# og14u.net
KiCad netlist of a schematic drawn in EAGLE
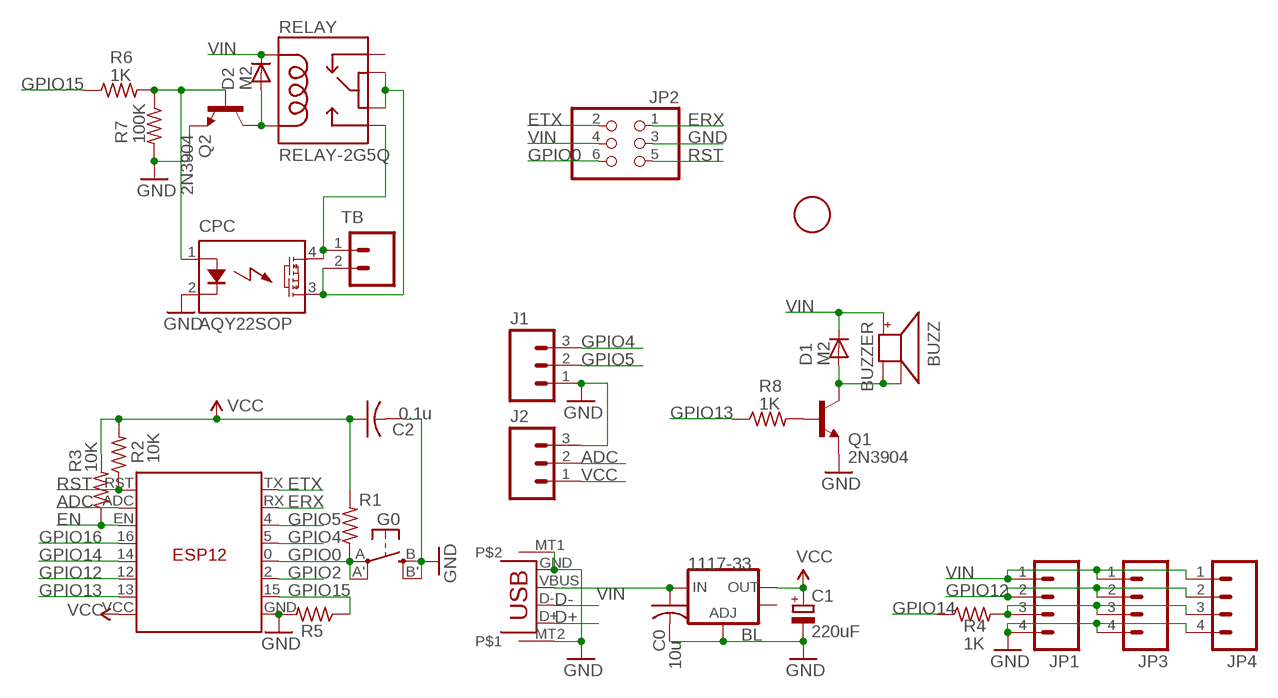
[diagram p0: schematic, sheet 1]

(export (version "E")
  (design (tool "Eeschema 10.0.6"))
  (components
    (comp (ref "1F")
      (value "FIDUCIAL")
      (footprint "eagle-import:FIDUCIAL_1MM")
      (libsource (lib "eagle-import") (part "FIDUCIAL"))
    )
    (comp (ref "BL")
      (value "1117-33")
      (footprint "eagle-import:SOT223")
      (libsource (lib "eagle-import") (part "V_REG_LM1117SOT223"))
    )
    (comp (ref "BUZZ")
      (value "BUZZER")
      (footprint "eagle-import:SMT-8585-BUZZER")
      (libsource (lib "eagle-import") (part "BUZZER"))
    )
    (comp (ref "C0")
      (value "10u")
      (footprint "eagle-import:C0805K")
      (libsource (lib "eagle-import") (part "C-USC0805K"))
    )
    (comp (ref "C1")
      (value "220uF")
      (footprint "eagle-import:B_3528-21R")
      (libsource (lib "eagle-import") (part "CPOL-EUB/3528-21R"))
    )
    (comp (ref "C2")
      (value "0.1u")
      (footprint "eagle-import:C0603K")
      (libsource (lib "eagle-import") (part "C-USC0603K"))
    )
    (comp (ref "CPC")
      (value "AQY22SOP")
      (footprint "eagle-import:SOP04")
      (libsource (lib "eagle-import") (part "AQYSOP22"))
    )
    (comp (ref "D1")
      (value "M2")
      (footprint "eagle-import:DO-214AC")
      (libsource (lib "eagle-import") (part "DIODE-DO-214AC"))
    )
    (comp (ref "D2")
      (value "M2")
      (footprint "eagle-import:DO-214AC")
      (libsource (lib "eagle-import") (part "DIODE-DO-214AC"))
    )
    (comp (ref "ESP")
      (value "ESP12")
      (footprint "eagle-import:ESP12")
      (libsource (lib "eagle-import") (part "ESP12"))
    )
    (comp (ref "G0")
      (value "SPST_TACT-EVQQ2")
      (footprint "eagle-import:EVQ-Q2")
      (libsource (lib "eagle-import") (part "SPST_TACT-EVQQ2"))
    )
    (comp (ref "J1")
      (value "M03PTH")
      (footprint "eagle-import:1X03")
      (libsource (lib "eagle-import") (part "M03PTH"))
    )
    (comp (ref "J2")
      (value "M03PTH")
      (footprint "eagle-import:1X03")
      (libsource (lib "eagle-import") (part "M03PTH"))
    )
    (comp (ref "JP1")
      (value "M04SONICSMD")
      (footprint "eagle-import:1X04_SONICSENSOR_SMD")
      (libsource (lib "eagle-import") (part "M04SONICSMD"))
    )
    (comp (ref "JP2")
      (value "PINHD-2X3")
      (footprint "eagle-import:2X03")
      (libsource (lib "eagle-import") (part "PINHD-2X3"))
    )
    (comp (ref "JP3")
      (value "M04DIST")
      (footprint "eagle-import:1X04_NO_SILK_DIST")
      (libsource (lib "eagle-import") (part "M04DIST"))
    )
    (comp (ref "JP4")
      (value "M04DIST")
      (footprint "eagle-import:1X04_NO_SILK_DIST")
      (libsource (lib "eagle-import") (part "M04DIST"))
    )
    (comp (ref "Q1")
      (value "2N3904")
      (footprint "eagle-import:SOT23-3")
      (libsource (lib "eagle-import") (part "TRANSISTOR_NPNSOT23-3"))
    )
    (comp (ref "Q2")
      (value "2N3904")
      (footprint "eagle-import:SOT23-3")
      (libsource (lib "eagle-import") (part "TRANSISTOR_NPNSOT23-3"))
    )
    (comp (ref "R1")
      (value "10K")
      (footprint "eagle-import:R0603")
      (libsource (lib "eagle-import") (part "R-US_R0603"))
    )
    (comp (ref "R2")
      (value "10K")
      (footprint "eagle-import:R0603")
      (libsource (lib "eagle-import") (part "R-US_R0603"))
    )
    (comp (ref "R3")
      (value "10K")
      (footprint "eagle-import:R0603")
      (libsource (lib "eagle-import") (part "R-US_R0603"))
    )
    (comp (ref "R4")
      (value "1K")
      (footprint "eagle-import:R0603")
      (libsource (lib "eagle-import") (part "adafruit2013_R-US_R0603"))
    )
    (comp (ref "R5")
      (value "10K")
      (footprint "eagle-import:R0603")
      (libsource (lib "eagle-import") (part "R-US_R0603"))
    )
    (comp (ref "R6")
      (value "1K")
      (footprint "eagle-import:R0603")
      (libsource (lib "eagle-import") (part "adafruit2013_R-US_R0603"))
    )
    (comp (ref "R7")
      (value "100K")
      (footprint "eagle-import:R0603")
      (libsource (lib "eagle-import") (part "adafruit2013_R-US_R0603"))
    )
    (comp (ref "R8")
      (value "1K")
      (footprint "eagle-import:R0603")
      (libsource (lib "eagle-import") (part "adafruit2013_R-US_R0603"))
    )
    (comp (ref "RELAY")
      (value "RELAY-2G5Q")
      (footprint "eagle-import:RELAY-G5V")
      (libsource (lib "eagle-import") (part "RELAY-2G5Q"))
    )
    (comp (ref "TB")
      (value "OPENER")
      (footprint "eagle-import:SCREWTERMINAL-5MM-2-KF")
      (libsource (lib "eagle-import") (part "M02KF"))
    )
    (comp (ref "X3")
      (value "USB+GND")
      (footprint "eagle-import:USB-MICROB2")
      (libsource (lib "eagle-import") (part "USB+GND"))
    )
  )
  (nets
    (net (code "1") (name "/ADC") (class "Default")
      (node (ref "ESP") (pin "ADC") (pinfunction "ADC_ADC") (pintype "bidirectional"))
      (node (ref "J2") (pin "2") (pinfunction "2_2") (pintype "passive"))
    )
    (net (code "2") (name "/D+") (class "Default")
      (node (ref "X3") (pin "D+") (pinfunction "D+_D+") (pintype "bidirectional"))
    )
    (net (code "3") (name "/D-") (class "Default")
      (node (ref "X3") (pin "D-") (pinfunction "D-_D-") (pintype "bidirectional"))
    )
    (net (code "4") (name "/EN") (class "Default")
      (node (ref "ESP") (pin "EN") (pinfunction "EN_EN") (pintype "bidirectional"))
      (node (ref "R3") (pin "1") (pinfunction "1_1") (pintype "passive"))
    )
    (net (code "5") (name "/ERX") (class "Default")
      (node (ref "ESP") (pin "RX") (pinfunction "RX_RX") (pintype "bidirectional"))
      (node (ref "JP2") (pin "1") (pinfunction "1_1") (pintype "passive"))
    )
    (net (code "6") (name "/ETX") (class "Default")
      (node (ref "ESP") (pin "TX") (pinfunction "TX_TX") (pintype "bidirectional"))
      (node (ref "JP2") (pin "2") (pinfunction "2_2") (pintype "passive"))
    )
    (net (code "7") (name "/GPIO0") (class "Default")
      (node (ref "ESP") (pin "0") (pinfunction "G0_0") (pintype "bidirectional"))
      (node (ref "G0") (pin "A") (pinfunction "P_A") (pintype "passive"))
      (node (ref "G0") (pin "A'") (pinfunction "P1_A'") (pintype "passive"))
      (node (ref "JP2") (pin "6") (pinfunction "6_6") (pintype "passive"))
      (node (ref "R1") (pin "1") (pinfunction "1_1") (pintype "passive"))
    )
    (net (code "8") (name "/GPIO2") (class "Default")
      (node (ref "ESP") (pin "2") (pinfunction "G2_2") (pintype "bidirectional"))
    )
    (net (code "9") (name "/GPIO4") (class "Default")
      (node (ref "ESP") (pin "5") (pinfunction "G5_5") (pintype "bidirectional"))
      (node (ref "J1") (pin "3") (pinfunction "3_3") (pintype "passive"))
    )
    (net (code "10") (name "/GPIO5") (class "Default")
      (node (ref "ESP") (pin "4") (pinfunction "G4_4") (pintype "bidirectional"))
      (node (ref "J1") (pin "2") (pinfunction "2_2") (pintype "passive"))
    )
    (net (code "11") (name "/GPIO12") (class "Default")
      (node (ref "ESP") (pin "12") (pinfunction "G12_12") (pintype "bidirectional"))
      (node (ref "JP1") (pin "2") (pinfunction "2_2") (pintype "passive"))
      (node (ref "JP3") (pin "2") (pinfunction "2_2") (pintype "passive"))
      (node (ref "JP4") (pin "2") (pinfunction "2_2") (pintype "passive"))
    )
    (net (code "12") (name "/GPIO13") (class "Default")
      (node (ref "ESP") (pin "13") (pinfunction "G13_13") (pintype "bidirectional"))
      (node (ref "R8") (pin "1") (pinfunction "1_1") (pintype "passive"))
    )
    (net (code "13") (name "/GPIO14") (class "Default")
      (node (ref "ESP") (pin "14") (pinfunction "G14_14") (pintype "bidirectional"))
      (node (ref "R4") (pin "1") (pinfunction "1_1") (pintype "passive"))
    )
    (net (code "14") (name "/GPIO15") (class "Default")
      (node (ref "ESP") (pin "15") (pinfunction "G15_15") (pintype "bidirectional"))
      (node (ref "R5") (pin "1") (pinfunction "1_1") (pintype "passive"))
      (node (ref "R6") (pin "1") (pinfunction "1_1") (pintype "passive"))
    )
    (net (code "15") (name "/GPIO16") (class "Default")
      (node (ref "ESP") (pin "16") (pinfunction "G16_16") (pintype "bidirectional"))
    )
    (net (code "16") (name "/RST") (class "Default")
      (node (ref "ESP") (pin "RST") (pinfunction "RST_RST") (pintype "bidirectional"))
      (node (ref "JP2") (pin "5") (pinfunction "5_5") (pintype "passive"))
      (node (ref "R2") (pin "1") (pinfunction "1_1") (pintype "passive"))
    )
    (net (code "17") (name "/VIN") (class "Default")
      (node (ref "BL") (pin "3") (pinfunction "IN_3") (pintype "input"))
      (node (ref "BUZZ") (pin "+") (pinfunction "+_+") (pintype "passive"))
      (node (ref "C0") (pin "1") (pinfunction "1_1") (pintype "passive"))
      (node (ref "D1") (pin "C") (pinfunction "C_C") (pintype "passive"))
      (node (ref "D2") (pin "C") (pinfunction "C_C") (pintype "passive"))
      (node (ref "JP1") (pin "1") (pinfunction "1_1") (pintype "passive"))
      (node (ref "JP2") (pin "4") (pinfunction "4_4") (pintype "passive"))
      (node (ref "JP3") (pin "1") (pinfunction "1_1") (pintype "passive"))
      (node (ref "JP4") (pin "1") (pinfunction "1_1") (pintype "passive"))
      (node (ref "RELAY") (pin "2") (pinfunction "2_2") (pintype "bidirectional"))
      (node (ref "X3") (pin "VBUS") (pinfunction "VBUS_VBUS") (pintype "bidirectional"))
    )
    (net (code "18") (name "GND") (class "Default")
      (node (ref "BL") (pin "1") (pinfunction "ADJ_1") (pintype "input"))
      (node (ref "C0") (pin "2") (pinfunction "2_2") (pintype "passive"))
      (node (ref "C1") (pin "-") (pinfunction "-_-") (pintype "passive"))
      (node (ref "C2") (pin "2") (pinfunction "2_2") (pintype "passive"))
      (node (ref "CPC") (pin "2") (pinfunction "K_2") (pintype "passive"))
      (node (ref "ESP") (pin "GND") (pinfunction "GND_GND") (pintype "power_in"))
      (node (ref "G0") (pin "B") (pinfunction "S_B") (pintype "passive"))
      (node (ref "G0") (pin "B'") (pinfunction "S1_B'") (pintype "passive"))
      (node (ref "J1") (pin "1") (pinfunction "1_1") (pintype "passive"))
      (node (ref "J2") (pin "3") (pinfunction "3_3") (pintype "passive"))
      (node (ref "JP1") (pin "4") (pinfunction "4_4") (pintype "passive"))
      (node (ref "JP2") (pin "3") (pinfunction "3_3") (pintype "passive"))
      (node (ref "JP3") (pin "4") (pinfunction "4_4") (pintype "passive"))
      (node (ref "JP4") (pin "4") (pinfunction "4_4") (pintype "passive"))
      (node (ref "Q1") (pin "2") (pinfunction "E_2") (pintype "passive"))
      (node (ref "Q2") (pin "2") (pinfunction "E_2") (pintype "passive"))
      (node (ref "R5") (pin "2") (pinfunction "2_2") (pintype "passive"))
      (node (ref "R7") (pin "2") (pinfunction "2_2") (pintype "passive"))
      (node (ref "X3") (pin "GND") (pinfunction "GND_GND") (pintype "bidirectional"))
      (node (ref "X3") (pin "MT1") (pinfunction "P$2_MT1") (pintype "bidirectional"))
      (node (ref "X3") (pin "MT2") (pinfunction "P$1_MT2") (pintype "bidirectional"))
    )
    (net (code "19") (name "Net-(CPC-A)") (class "Default")
      (node (ref "CPC") (pin "1") (pinfunction "A_1") (pintype "passive"))
      (node (ref "Q2") (pin "1") (pinfunction "B_1") (pintype "passive"))
      (node (ref "R6") (pin "2") (pinfunction "2_2") (pintype "passive"))
      (node (ref "R7") (pin "1") (pinfunction "1_1") (pintype "passive"))
    )
    (net (code "20") (name "Net-(CPC-DS1)") (class "Default")
      (node (ref "CPC") (pin "4") (pinfunction "DS1_4") (pintype "passive"))
      (node (ref "RELAY") (pin "10") (pinfunction "10_10") (pintype "bidirectional"))
      (node (ref "TB") (pin "1") (pinfunction "1_1") (pintype "passive"))
    )
    (net (code "21") (name "Net-(CPC-DS2)") (class "Default")
      (node (ref "CPC") (pin "3") (pinfunction "DS2_3") (pintype "passive"))
      (node (ref "RELAY") (pin "5") (pinfunction "5_5") (pintype "bidirectional"))
      (node (ref "RELAY") (pin "6") (pinfunction "6_6") (pintype "bidirectional"))
      (node (ref "TB") (pin "2") (pinfunction "2_2") (pintype "passive"))
    )
    (net (code "22") (name "Net-(JP1-Pad3)") (class "Default")
      (node (ref "JP1") (pin "3") (pinfunction "3_3") (pintype "passive"))
      (node (ref "JP3") (pin "3") (pinfunction "3_3") (pintype "passive"))
      (node (ref "JP4") (pin "3") (pinfunction "3_3") (pintype "passive"))
      (node (ref "R4") (pin "2") (pinfunction "2_2") (pintype "passive"))
    )
    (net (code "23") (name "Net-(Q1-B)") (class "Default")
      (node (ref "Q1") (pin "1") (pinfunction "B_1") (pintype "passive"))
      (node (ref "R8") (pin "2") (pinfunction "2_2") (pintype "passive"))
    )
    (net (code "24") (name "Net-(Q1-C)") (class "Default")
      (node (ref "BUZZ") (pin "-") (pinfunction "-_-") (pintype "passive"))
      (node (ref "BUZZ") (pin "A-") (pinfunction "A-_A-") (pintype "passive"))
      (node (ref "D1") (pin "A") (pinfunction "A_A") (pintype "passive"))
      (node (ref "Q1") (pin "3") (pinfunction "C_3") (pintype "passive"))
    )
    (net (code "25") (name "Net-(Q2-C)") (class "Default")
      (node (ref "D2") (pin "A") (pinfunction "A_A") (pintype "passive"))
      (node (ref "Q2") (pin "3") (pinfunction "C_3") (pintype "passive"))
      (node (ref "RELAY") (pin "9") (pinfunction "9_9") (pintype "bidirectional"))
    )
    (net (code "26") (name "VCC") (class "Default")
      (node (ref "BL") (pin "2") (pinfunction "OUT_2") (pintype "bidirectional"))
      (node (ref "C1") (pin "+") (pinfunction "+_+") (pintype "passive"))
      (node (ref "C2") (pin "1") (pinfunction "1_1") (pintype "passive"))
      (node (ref "ESP") (pin "VCC") (pinfunction "VCC_VCC") (pintype "power_in"))
      (node (ref "J2") (pin "1") (pinfunction "1_1") (pintype "passive"))
      (node (ref "R1") (pin "2") (pinfunction "2_2") (pintype "passive"))
      (node (ref "R2") (pin "2") (pinfunction "2_2") (pintype "passive"))
      (node (ref "R3") (pin "2") (pinfunction "2_2") (pintype "passive"))
    )
    (net (code "27") (name "unconnected-(BL-OUT-Pad4)") (class "Default")
      (node (ref "BL") (pin "4") (pinfunction "OUT_4") (pintype "bidirectional"))
    )
    (net (code "28") (name "unconnected-(RELAY-Pad1)") (class "Default")
      (node (ref "RELAY") (pin "1") (pinfunction "1_1") (pintype "bidirectional"))
    )
  )
)
